# nano_bt_hor.net
KiCad netlist of a schematic drawn in EAGLE
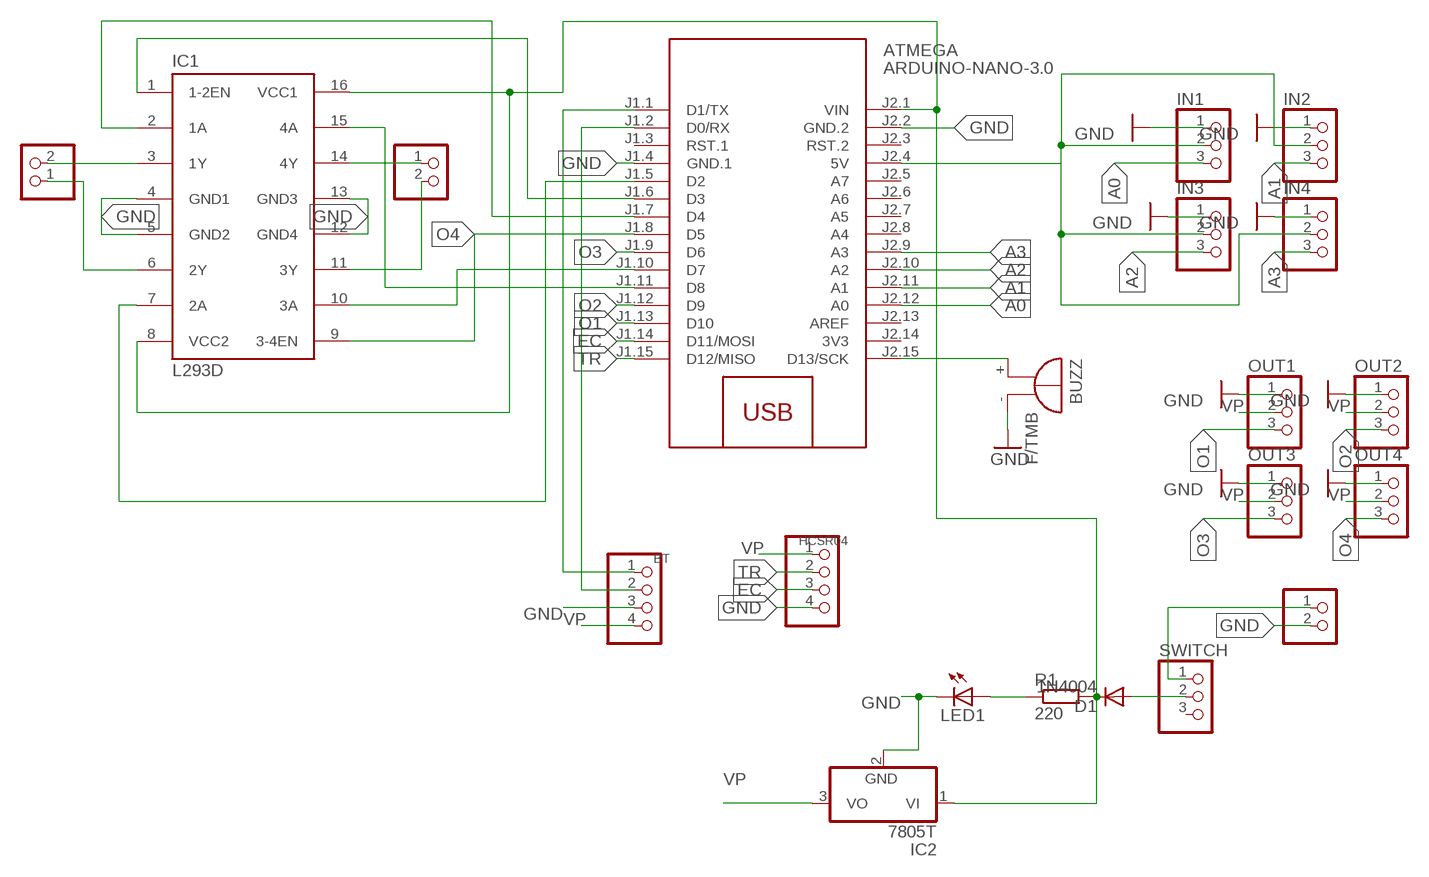
[diagram p0: schematic, sheet 1]

(export (version "E")
  (design (tool "Eeschema 10.0.6"))
  (components
    (comp (ref "ATMEGA")
      (value "ARDUINO-NANO-3.0")
      (footprint "eagle-import:ARDUINO-NANO-3.0")
      (libsource (lib "eagle-import") (part "ARDUINO-NANO-3.0"))
    )
    (comp (ref "BT")
      (value "PINHD-1X4")
      (footprint "eagle-import:1X04")
      (libsource (lib "eagle-import") (part "PINHD-1X4"))
    )
    (comp (ref "BUZZ")
      (value "F/TMB")
      (footprint "eagle-import:F_TMB")
      (libsource (lib "eagle-import") (part "F/TMB"))
    )
    (comp (ref "D1")
      (value "1N4004")
      (footprint "eagle-import:DO41-10")
      (libsource (lib "eagle-import") (part "1N4004"))
    )
    (comp (ref "DCV")
      (value "PINHD-1X2")
      (footprint "eagle-import:1X02")
      (libsource (lib "eagle-import") (part "PINHD-1X2"))
    )
    (comp (ref "HCSR04")
      (value "PINHD-1X4")
      (footprint "eagle-import:1X04")
      (libsource (lib "eagle-import") (part "PINHD-1X4"))
    )
    (comp (ref "IC1")
      (value "L293D")
      (footprint "eagle-import:DIL16")
      (libsource (lib "eagle-import") (part "L293D"))
    )
    (comp (ref "IC2")
      (value "7805T")
      (footprint "eagle-import:TO220H")
      (libsource (lib "eagle-import") (part "78T05"))
    )
    (comp (ref "IN1")
      (value "PINHD-1X3")
      (footprint "eagle-import:1X03")
      (libsource (lib "eagle-import") (part "PINHD-1X3"))
    )
    (comp (ref "IN2")
      (value "PINHD-1X3")
      (footprint "eagle-import:1X03")
      (libsource (lib "eagle-import") (part "PINHD-1X3"))
    )
    (comp (ref "IN3")
      (value "PINHD-1X3")
      (footprint "eagle-import:1X03")
      (libsource (lib "eagle-import") (part "PINHD-1X3"))
    )
    (comp (ref "IN4")
      (value "PINHD-1X3")
      (footprint "eagle-import:1X03")
      (libsource (lib "eagle-import") (part "PINHD-1X3"))
    )
    (comp (ref "LED1")
      (value "LED3MM")
      (footprint "eagle-import:LED3MM")
      (libsource (lib "eagle-import") (part "LED3MM"))
    )
    (comp (ref "MT1")
      (value "PINHD-1X2")
      (footprint "eagle-import:1X02")
      (libsource (lib "eagle-import") (part "PINHD-1X2"))
    )
    (comp (ref "MT2")
      (value "PINHD-1X2")
      (footprint "eagle-import:1X02")
      (libsource (lib "eagle-import") (part "PINHD-1X2"))
    )
    (comp (ref "OUT1")
      (value "PINHD-1X3")
      (footprint "eagle-import:1X03")
      (libsource (lib "eagle-import") (part "PINHD-1X3"))
    )
    (comp (ref "OUT2")
      (value "PINHD-1X3")
      (footprint "eagle-import:1X03")
      (libsource (lib "eagle-import") (part "PINHD-1X3"))
    )
    (comp (ref "OUT3")
      (value "PINHD-1X3")
      (footprint "eagle-import:1X03")
      (libsource (lib "eagle-import") (part "PINHD-1X3"))
    )
    (comp (ref "OUT4")
      (value "PINHD-1X3")
      (footprint "eagle-import:1X03")
      (libsource (lib "eagle-import") (part "PINHD-1X3"))
    )
    (comp (ref "R1")
      (value "220")
      (footprint "eagle-import:0204_7")
      (libsource (lib "eagle-import") (part "R-EU_0204/7"))
    )
    (comp (ref "SWITCH")
      (value "PINHD-1X3")
      (footprint "eagle-import:1X03")
      (libsource (lib "eagle-import") (part "adafruit_arduino_PINHD-1X3"))
    )
  )
  (nets
    (net (code "1") (name "/3V3") (class "Default")
      (node (ref "ATMEGA") (pin "J2.14") (pinfunction "3V3_J2.14") (pintype "power_in"))
    )
    (net (code "2") (name "/VP") (class "Default")
      (node (ref "BT") (pin "4") (pinfunction "4_4") (pintype "passive"))
      (node (ref "HCSR04") (pin "1") (pinfunction "1_1") (pintype "passive"))
      (node (ref "IC2") (pin "3") (pinfunction "VO_3") (pintype "passive"))
      (node (ref "OUT1") (pin "2") (pinfunction "2_2") (pintype "passive"))
      (node (ref "OUT2") (pin "2") (pinfunction "2_2") (pintype "passive"))
      (node (ref "OUT3") (pin "2") (pinfunction "2_2") (pintype "passive"))
      (node (ref "OUT4") (pin "2") (pinfunction "2_2") (pintype "passive"))
    )
    (net (code "3") (name "A0") (class "Default")
      (node (ref "ATMEGA") (pin "J2.12") (pinfunction "A0_J2.12") (pintype "bidirectional"))
      (node (ref "IN1") (pin "3") (pinfunction "3_3") (pintype "passive"))
    )
    (net (code "4") (name "A1") (class "Default")
      (node (ref "ATMEGA") (pin "J2.11") (pinfunction "A1_J2.11") (pintype "bidirectional"))
      (node (ref "IN2") (pin "3") (pinfunction "3_3") (pintype "passive"))
    )
    (net (code "5") (name "A2") (class "Default")
      (node (ref "ATMEGA") (pin "J2.10") (pinfunction "A2_J2.10") (pintype "bidirectional"))
      (node (ref "IN3") (pin "3") (pinfunction "3_3") (pintype "passive"))
    )
    (net (code "6") (name "A3") (class "Default")
      (node (ref "ATMEGA") (pin "J2.9") (pinfunction "A3_J2.9") (pintype "bidirectional"))
      (node (ref "IN4") (pin "3") (pinfunction "3_3") (pintype "passive"))
    )
    (net (code "7") (name "EC") (class "Default")
      (node (ref "ATMEGA") (pin "J1.14") (pinfunction "D11/MOSI_J1.14") (pintype "bidirectional"))
      (node (ref "HCSR04") (pin "3") (pinfunction "3_3") (pintype "passive"))
    )
    (net (code "8") (name "GND") (class "Default")
      (node (ref "ATMEGA") (pin "J1.4") (pinfunction "GND.1_J1.4") (pintype "power_in"))
      (node (ref "ATMEGA") (pin "J2.2") (pinfunction "GND.2_J2.2") (pintype "power_in"))
      (node (ref "BT") (pin "3") (pinfunction "3_3") (pintype "passive"))
      (node (ref "BUZZ") (pin "-") (pinfunction "-_-") (pintype "passive"))
      (node (ref "DCV") (pin "2") (pinfunction "2_2") (pintype "passive"))
      (node (ref "HCSR04") (pin "4") (pinfunction "4_4") (pintype "passive"))
      (node (ref "IC1") (pin "12") (pinfunction "GND4_12") (pintype "power_in"))
      (node (ref "IC1") (pin "13") (pinfunction "GND3_13") (pintype "power_in"))
      (node (ref "IC1") (pin "4") (pinfunction "GND1_4") (pintype "power_in"))
      (node (ref "IC1") (pin "5") (pinfunction "GND2_5") (pintype "power_in"))
      (node (ref "IC2") (pin "2") (pinfunction "GND_2") (pintype "passive"))
      (node (ref "IN1") (pin "1") (pinfunction "1_1") (pintype "passive"))
      (node (ref "IN2") (pin "1") (pinfunction "1_1") (pintype "passive"))
      (node (ref "IN3") (pin "1") (pinfunction "1_1") (pintype "passive"))
      (node (ref "IN4") (pin "1") (pinfunction "1_1") (pintype "passive"))
      (node (ref "LED1") (pin "K") (pinfunction "C_K") (pintype "passive"))
      (node (ref "OUT1") (pin "1") (pinfunction "1_1") (pintype "passive"))
      (node (ref "OUT2") (pin "1") (pinfunction "1_1") (pintype "passive"))
      (node (ref "OUT3") (pin "1") (pinfunction "1_1") (pintype "passive"))
      (node (ref "OUT4") (pin "1") (pinfunction "1_1") (pintype "passive"))
    )
    (net (code "9") (name "Net-(ATMEGA-5V)") (class "Default")
      (node (ref "ATMEGA") (pin "J2.4") (pinfunction "5V_J2.4") (pintype "power_in"))
      (node (ref "IN1") (pin "2") (pinfunction "2_2") (pintype "passive"))
      (node (ref "IN2") (pin "2") (pinfunction "2_2") (pintype "passive"))
      (node (ref "IN3") (pin "2") (pinfunction "2_2") (pintype "passive"))
      (node (ref "IN4") (pin "2") (pinfunction "2_2") (pintype "passive"))
    )
    (net (code "10") (name "Net-(ATMEGA-D0{slash}RX)") (class "Default")
      (node (ref "ATMEGA") (pin "J1.2") (pinfunction "D0/RX_J1.2") (pintype "bidirectional"))
      (node (ref "BT") (pin "2") (pinfunction "2_2") (pintype "passive"))
    )
    (net (code "11") (name "Net-(ATMEGA-D1{slash}TX)") (class "Default")
      (node (ref "ATMEGA") (pin "J1.1") (pinfunction "D1/TX_J1.1") (pintype "bidirectional"))
      (node (ref "BT") (pin "1") (pinfunction "1_1") (pintype "passive"))
    )
    (net (code "12") (name "Net-(ATMEGA-D2)") (class "Default")
      (node (ref "ATMEGA") (pin "J1.5") (pinfunction "D2_J1.5") (pintype "bidirectional"))
      (node (ref "IC1") (pin "7") (pinfunction "2A_7") (pintype "input"))
    )
    (net (code "13") (name "Net-(ATMEGA-D3)") (class "Default")
      (node (ref "ATMEGA") (pin "J1.6") (pinfunction "D3_J1.6") (pintype "bidirectional"))
      (node (ref "IC1") (pin "1") (pinfunction "1-2EN_1") (pintype "input"))
    )
    (net (code "14") (name "Net-(ATMEGA-D4)") (class "Default")
      (node (ref "ATMEGA") (pin "J1.7") (pinfunction "D4_J1.7") (pintype "bidirectional"))
      (node (ref "IC1") (pin "2") (pinfunction "1A_2") (pintype "input"))
    )
    (net (code "15") (name "Net-(ATMEGA-D7)") (class "Default")
      (node (ref "ATMEGA") (pin "J1.10") (pinfunction "D7_J1.10") (pintype "bidirectional"))
      (node (ref "IC1") (pin "10") (pinfunction "3A_10") (pintype "input"))
    )
    (net (code "16") (name "Net-(ATMEGA-D8)") (class "Default")
      (node (ref "ATMEGA") (pin "J1.11") (pinfunction "D8_J1.11") (pintype "bidirectional"))
      (node (ref "IC1") (pin "15") (pinfunction "4A_15") (pintype "input"))
    )
    (net (code "17") (name "Net-(ATMEGA-D13{slash}SCK)") (class "Default")
      (node (ref "ATMEGA") (pin "J2.15") (pinfunction "D13/SCK_J2.15") (pintype "bidirectional"))
      (node (ref "BUZZ") (pin "+") (pinfunction "+_+") (pintype "passive"))
    )
    (net (code "18") (name "Net-(ATMEGA-VIN)") (class "Default")
      (node (ref "ATMEGA") (pin "J2.1") (pinfunction "VIN_J2.1") (pintype "power_in"))
      (node (ref "D1") (pin "C") (pinfunction "C_C") (pintype "passive"))
      (node (ref "IC1") (pin "16") (pinfunction "VCC1_16") (pintype "power_in"))
      (node (ref "IC1") (pin "8") (pinfunction "VCC2_8") (pintype "power_in"))
      (node (ref "IC2") (pin "1") (pinfunction "VI_1") (pintype "input"))
      (node (ref "R1") (pin "2") (pinfunction "2_2") (pintype "passive"))
    )
    (net (code "19") (name "Net-(D1-PadA)") (class "Default")
      (node (ref "D1") (pin "A") (pinfunction "A_A") (pintype "passive"))
      (node (ref "SWITCH") (pin "2") (pinfunction "2_2") (pintype "passive"))
    )
    (net (code "20") (name "Net-(DCV-Pad1)") (class "Default")
      (node (ref "DCV") (pin "1") (pinfunction "1_1") (pintype "passive"))
      (node (ref "SWITCH") (pin "1") (pinfunction "1_1") (pintype "passive"))
    )
    (net (code "21") (name "Net-(IC1-1Y)") (class "Default")
      (node (ref "IC1") (pin "3") (pinfunction "1Y_3") (pintype "output"))
      (node (ref "MT1") (pin "2") (pinfunction "2_2") (pintype "passive"))
    )
    (net (code "22") (name "Net-(IC1-2Y)") (class "Default")
      (node (ref "IC1") (pin "6") (pinfunction "2Y_6") (pintype "output"))
      (node (ref "MT1") (pin "1") (pinfunction "1_1") (pintype "passive"))
    )
    (net (code "23") (name "Net-(IC1-3Y)") (class "Default")
      (node (ref "IC1") (pin "11") (pinfunction "3Y_11") (pintype "output"))
      (node (ref "MT2") (pin "2") (pinfunction "2_2") (pintype "passive"))
    )
    (net (code "24") (name "Net-(IC1-4Y)") (class "Default")
      (node (ref "IC1") (pin "14") (pinfunction "4Y_14") (pintype "output"))
      (node (ref "MT2") (pin "1") (pinfunction "1_1") (pintype "passive"))
    )
    (net (code "25") (name "Net-(LED1-PadA)") (class "Default")
      (node (ref "LED1") (pin "A") (pinfunction "A_A") (pintype "passive"))
      (node (ref "R1") (pin "1") (pinfunction "1_1") (pintype "passive"))
    )
    (net (code "26") (name "O1") (class "Default")
      (node (ref "ATMEGA") (pin "J1.13") (pinfunction "D10_J1.13") (pintype "bidirectional"))
      (node (ref "OUT1") (pin "3") (pinfunction "3_3") (pintype "passive"))
    )
    (net (code "27") (name "O2") (class "Default")
      (node (ref "ATMEGA") (pin "J1.12") (pinfunction "D9_J1.12") (pintype "bidirectional"))
      (node (ref "OUT2") (pin "3") (pinfunction "3_3") (pintype "passive"))
    )
    (net (code "28") (name "O3") (class "Default")
      (node (ref "ATMEGA") (pin "J1.9") (pinfunction "D6_J1.9") (pintype "bidirectional"))
      (node (ref "OUT3") (pin "3") (pinfunction "3_3") (pintype "passive"))
    )
    (net (code "29") (name "O4") (class "Default")
      (node (ref "ATMEGA") (pin "J1.8") (pinfunction "D5_J1.8") (pintype "bidirectional"))
      (node (ref "IC1") (pin "9") (pinfunction "3-4EN_9") (pintype "input"))
      (node (ref "OUT4") (pin "3") (pinfunction "3_3") (pintype "passive"))
    )
    (net (code "30") (name "TR") (class "Default")
      (node (ref "ATMEGA") (pin "J1.15") (pinfunction "D12/MISO_J1.15") (pintype "bidirectional"))
      (node (ref "HCSR04") (pin "2") (pinfunction "2_2") (pintype "passive"))
    )
    (net (code "31") (name "unconnected-(ATMEGA-A4-PadJ2.8)") (class "Default")
      (node (ref "ATMEGA") (pin "J2.8") (pinfunction "A4_J2.8") (pintype "bidirectional"))
    )
    (net (code "32") (name "unconnected-(ATMEGA-A5-PadJ2.7)") (class "Default")
      (node (ref "ATMEGA") (pin "J2.7") (pinfunction "A5_J2.7") (pintype "bidirectional"))
    )
    (net (code "33") (name "unconnected-(ATMEGA-A6-PadJ2.6)") (class "Default")
      (node (ref "ATMEGA") (pin "J2.6") (pinfunction "A6_J2.6") (pintype "bidirectional"))
    )
    (net (code "34") (name "unconnected-(ATMEGA-A7-PadJ2.5)") (class "Default")
      (node (ref "ATMEGA") (pin "J2.5") (pinfunction "A7_J2.5") (pintype "bidirectional"))
    )
    (net (code "35") (name "unconnected-(ATMEGA-AREF-PadJ2.13)") (class "Default")
      (node (ref "ATMEGA") (pin "J2.13") (pinfunction "AREF_J2.13") (pintype "bidirectional"))
    )
    (net (code "36") (name "unconnected-(ATMEGA-RST.1-PadJ1.3)") (class "Default")
      (node (ref "ATMEGA") (pin "J1.3") (pinfunction "RST.1_J1.3") (pintype "bidirectional"))
    )
    (net (code "37") (name "unconnected-(ATMEGA-RST.2-PadJ2.3)") (class "Default")
      (node (ref "ATMEGA") (pin "J2.3") (pinfunction "RST.2_J2.3") (pintype "bidirectional"))
    )
    (net (code "38") (name "unconnected-(SWITCH-Pad3)") (class "Default")
      (node (ref "SWITCH") (pin "3") (pinfunction "3_3") (pintype "passive"))
    )
  )
)
